# RK3562-POWER-GND.net
KiCad netlist of a schematic drawn in Altium Designer
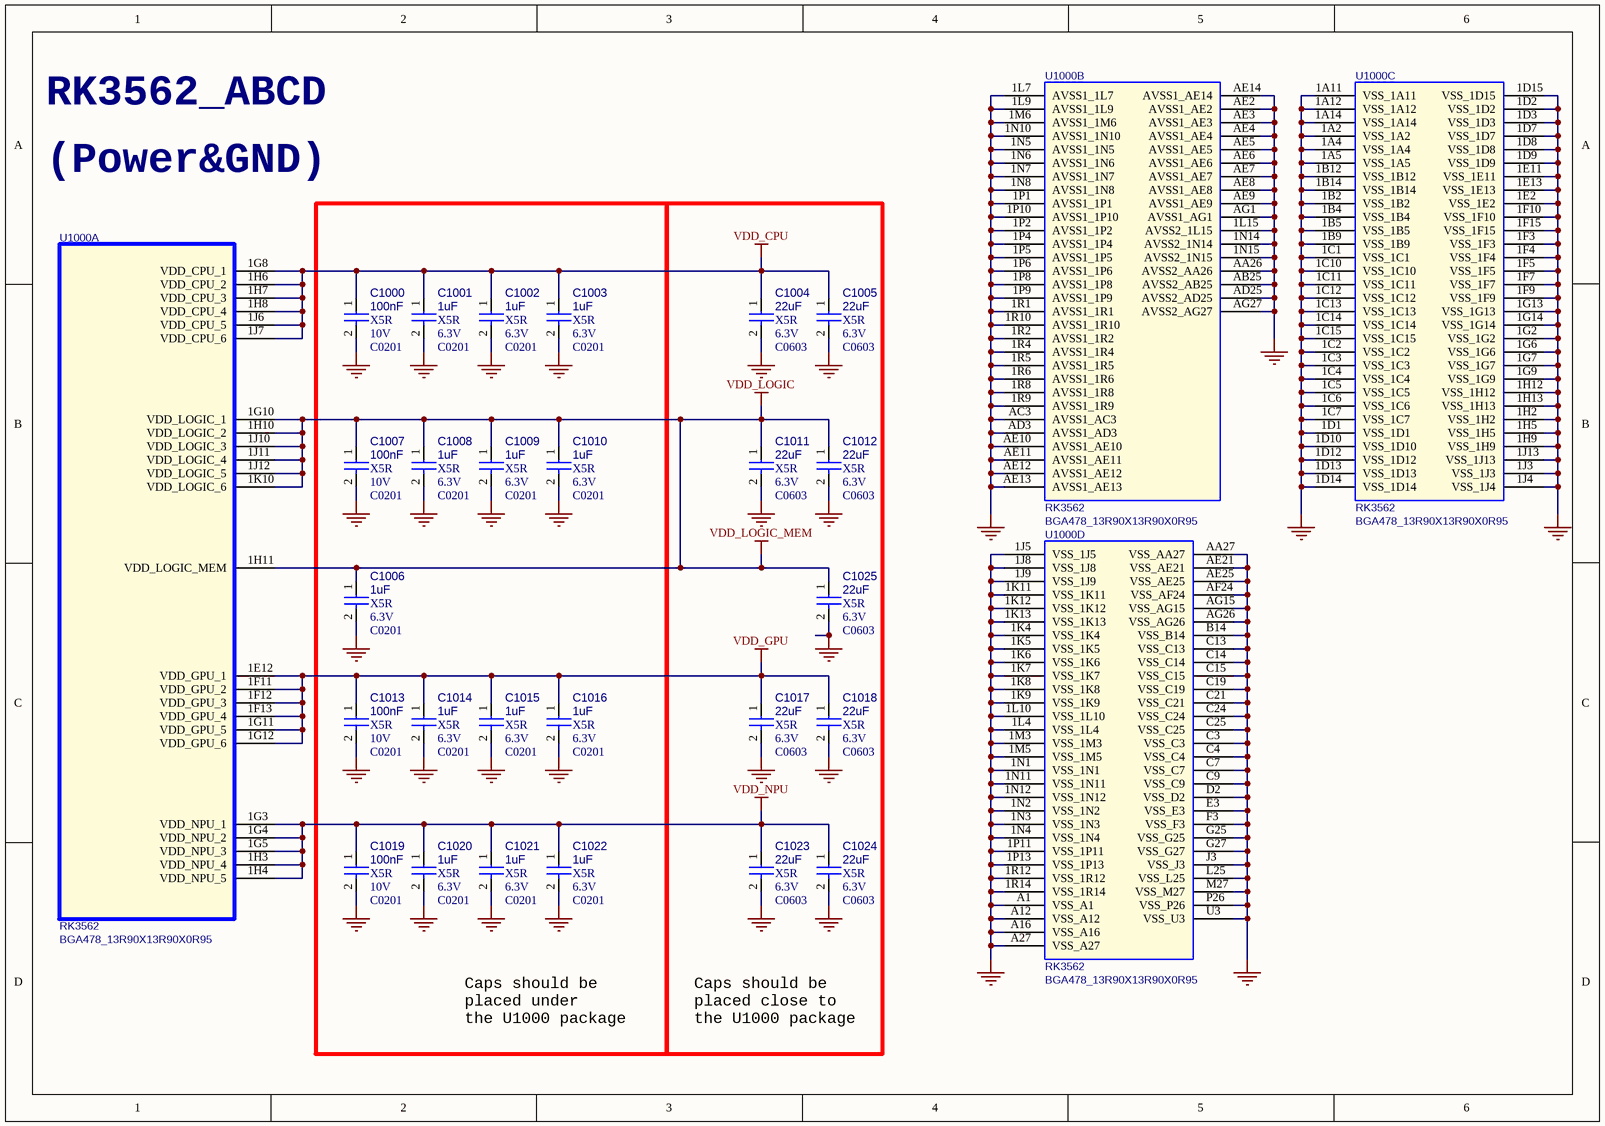
[diagram p0: RK3562-POWER-GND.SchDoc]

(export (version "E")
  (design (tool "Eeschema 10.0.6"))
  (components
    (comp (ref "C1000")
      (value "100nF")
      (footprint "C0201")
      (description "cap,100.00nF,+/-10%,10V,X5R,C0201")
      (fields
        (field (name "DIELECTRIC") "X5R")
        (field (name "PCB FOOTPRINT") "C0201")
        (field (name "VOLTAGE") "10V")
        (field (name "MANUFACTURER") "TDK")
        (field (name "TOLERANCE") "10%")
        (field (name "CREATED BY") "JJJ")
      )
      (libsource (lib "RK3562_REF") (part "CAP NP"))
    )
    (comp (ref "C1001")
      (value "1uF")
      (footprint "C0201")
      (description "cap,1.00uF,+/-20%,6.3V,X5R,C0201")
      (fields
        (field (name "DIELECTRIC") "X5R")
        (field (name "PCB FOOTPRINT") "C0201")
        (field (name "VOLTAGE") "6.3V")
        (field (name "TOLERANCE") "20%")
        (field (name "MANUFACTURER") "TDK")
        (field (name "CREATED BY") "JJJ")
      )
      (libsource (lib "RK3562_REF") (part "CAP NP"))
    )
    (comp (ref "C1002")
      (value "1uF")
      (footprint "C0201")
      (description "cap,1.00uF,+/-20%,6.3V,X5R,C0201")
      (fields
        (field (name "DIELECTRIC") "X5R")
        (field (name "PCB FOOTPRINT") "C0201")
        (field (name "VOLTAGE") "6.3V")
        (field (name "MANUFACTURER") "TDK")
        (field (name "TOLERANCE") "20%")
        (field (name "CREATED BY") "JJJ")
      )
      (libsource (lib "RK3562_REF") (part "CAP NP"))
    )
    (comp (ref "C1003")
      (value "1uF")
      (footprint "C0201")
      (description "cap,1.00uF,+/-20%,6.3V,X5R,C0201")
      (fields
        (field (name "DIELECTRIC") "X5R")
        (field (name "PCB FOOTPRINT") "C0201")
        (field (name "VOLTAGE") "6.3V")
        (field (name "MANUFACTURER") "TDK")
        (field (name "TOLERANCE") "20%")
        (field (name "CREATED BY") "JJJ")
      )
      (libsource (lib "RK3562_REF") (part "CAP NP"))
    )
    (comp (ref "C1004")
      (value "22uF")
      (footprint "C0603")
      (description "cap,22.00uF,+/-20%,6.3V,X5R,C0603")
      (fields
        (field (name "DIELECTRIC") "X5R")
        (field (name "PCB FOOTPRINT") "C0603")
        (field (name "VOLTAGE") "6.3V")
        (field (name "MANUFACTURER") "TDK")
        (field (name "TOLERANCE") "20%")
        (field (name "CREATED BY") "JJJ")
      )
      (libsource (lib "RK3562_REF") (part "CAP NP"))
    )
    (comp (ref "C1005")
      (value "22uF")
      (footprint "C0603")
      (description "cap,22.00uF,+/-20%,6.3V,X5R,C0603")
      (fields
        (field (name "DIELECTRIC") "X5R")
        (field (name "PCB FOOTPRINT") "C0603")
        (field (name "VOLTAGE") "6.3V")
        (field (name "MANUFACTURER") "TDK")
        (field (name "TOLERANCE") "20%")
        (field (name "CREATED BY") "JJJ")
      )
      (libsource (lib "RK3562_REF") (part "CAP NP"))
    )
    (comp (ref "C1006")
      (value "1uF")
      (footprint "C0201")
      (description "cap,1.00uF,+/-20%,6.3V,X5R,C0201")
      (fields
        (field (name "DIELECTRIC") "X5R")
        (field (name "PCB FOOTPRINT") "C0201")
        (field (name "VOLTAGE") "6.3V")
        (field (name "MANUFACTURER") "TDK")
        (field (name "TOLERANCE") "20%")
        (field (name "CREATED BY") "JJJ")
      )
      (libsource (lib "RK3562_REF") (part "CAP NP"))
    )
    (comp (ref "C1007")
      (value "100nF")
      (footprint "C0201")
      (description "cap,100.00nF,+/-10%,10V,X5R,C0201")
      (fields
        (field (name "DIELECTRIC") "X5R")
        (field (name "PCB FOOTPRINT") "C0201")
        (field (name "VOLTAGE") "10V")
        (field (name "MANUFACTURER") "TDK")
        (field (name "TOLERANCE") "10%")
        (field (name "CREATED BY") "JJJ")
      )
      (libsource (lib "RK3562_REF") (part "CAP NP"))
    )
    (comp (ref "C1008")
      (value "1uF")
      (footprint "C0201")
      (description "cap,1.00uF,+/-20%,6.3V,X5R,C0201")
      (fields
        (field (name "DIELECTRIC") "X5R")
        (field (name "PCB FOOTPRINT") "C0201")
        (field (name "VOLTAGE") "6.3V")
        (field (name "TOLERANCE") "20%")
        (field (name "MANUFACTURER") "TDK")
        (field (name "CREATED BY") "JJJ")
      )
      (libsource (lib "RK3562_REF") (part "CAP NP"))
    )
    (comp (ref "C1009")
      (value "1uF")
      (footprint "C0201")
      (description "cap,1.00uF,+/-20%,6.3V,X5R,C0201")
      (fields
        (field (name "DIELECTRIC") "X5R")
        (field (name "PCB FOOTPRINT") "C0201")
        (field (name "VOLTAGE") "6.3V")
        (field (name "MANUFACTURER") "TDK")
        (field (name "TOLERANCE") "20%")
        (field (name "CREATED BY") "JJJ")
      )
      (libsource (lib "RK3562_REF") (part "CAP NP"))
    )
    (comp (ref "C1010")
      (value "1uF")
      (footprint "C0201")
      (description "cap,1.00uF,+/-20%,6.3V,X5R,C0201")
      (fields
        (field (name "DIELECTRIC") "X5R")
        (field (name "PCB FOOTPRINT") "C0201")
        (field (name "VOLTAGE") "6.3V")
        (field (name "MANUFACTURER") "TDK")
        (field (name "TOLERANCE") "20%")
        (field (name "CREATED BY") "JJJ")
      )
      (libsource (lib "RK3562_REF") (part "CAP NP"))
    )
    (comp (ref "C1011")
      (value "22uF")
      (footprint "C0603")
      (description "cap,22.00uF,+/-20%,6.3V,X5R,C0603")
      (fields
        (field (name "DIELECTRIC") "X5R")
        (field (name "PCB FOOTPRINT") "C0603")
        (field (name "VOLTAGE") "6.3V")
        (field (name "MANUFACTURER") "TDK")
        (field (name "TOLERANCE") "20%")
        (field (name "CREATED BY") "JJJ")
      )
      (libsource (lib "RK3562_REF") (part "CAP NP"))
    )
    (comp (ref "C1012")
      (value "22uF")
      (footprint "C0603")
      (description "cap,22.00uF,+/-20%,6.3V,X5R,C0603")
      (fields
        (field (name "DIELECTRIC") "X5R")
        (field (name "PCB FOOTPRINT") "C0603")
        (field (name "VOLTAGE") "6.3V")
        (field (name "MANUFACTURER") "TDK")
        (field (name "TOLERANCE") "20%")
        (field (name "CREATED BY") "JJJ")
      )
      (libsource (lib "RK3562_REF") (part "CAP NP"))
    )
    (comp (ref "C1013")
      (value "100nF")
      (footprint "C0201")
      (description "cap,100.00nF,+/-10%,10V,X5R,C0201")
      (fields
        (field (name "DIELECTRIC") "X5R")
        (field (name "PCB FOOTPRINT") "C0201")
        (field (name "VOLTAGE") "10V")
        (field (name "MANUFACTURER") "TDK")
        (field (name "TOLERANCE") "10%")
        (field (name "CREATED BY") "JJJ")
      )
      (libsource (lib "RK3562_REF") (part "CAP NP"))
    )
    (comp (ref "C1014")
      (value "1uF")
      (footprint "C0201")
      (description "cap,1.00uF,+/-20%,6.3V,X5R,C0201")
      (fields
        (field (name "DIELECTRIC") "X5R")
        (field (name "PCB FOOTPRINT") "C0201")
        (field (name "VOLTAGE") "6.3V")
        (field (name "TOLERANCE") "20%")
        (field (name "MANUFACTURER") "TDK")
        (field (name "CREATED BY") "JJJ")
      )
      (libsource (lib "RK3562_REF") (part "CAP NP"))
    )
    (comp (ref "C1015")
      (value "1uF")
      (footprint "C0201")
      (description "cap,1.00uF,+/-20%,6.3V,X5R,C0201")
      (fields
        (field (name "DIELECTRIC") "X5R")
        (field (name "PCB FOOTPRINT") "C0201")
        (field (name "VOLTAGE") "6.3V")
        (field (name "MANUFACTURER") "TDK")
        (field (name "TOLERANCE") "20%")
        (field (name "CREATED BY") "JJJ")
      )
      (libsource (lib "RK3562_REF") (part "CAP NP"))
    )
    (comp (ref "C1016")
      (value "1uF")
      (footprint "C0201")
      (description "cap,1.00uF,+/-20%,6.3V,X5R,C0201")
      (fields
        (field (name "DIELECTRIC") "X5R")
        (field (name "PCB FOOTPRINT") "C0201")
        (field (name "VOLTAGE") "6.3V")
        (field (name "MANUFACTURER") "TDK")
        (field (name "TOLERANCE") "20%")
        (field (name "CREATED BY") "JJJ")
      )
      (libsource (lib "RK3562_REF") (part "CAP NP"))
    )
    (comp (ref "C1017")
      (value "22uF")
      (footprint "C0603")
      (description "cap,22.00uF,+/-20%,6.3V,X5R,C0603")
      (fields
        (field (name "DIELECTRIC") "X5R")
        (field (name "PCB FOOTPRINT") "C0603")
        (field (name "VOLTAGE") "6.3V")
        (field (name "MANUFACTURER") "TDK")
        (field (name "TOLERANCE") "20%")
        (field (name "CREATED BY") "JJJ")
      )
      (libsource (lib "RK3562_REF") (part "CAP NP"))
    )
    (comp (ref "C1018")
      (value "22uF")
      (footprint "C0603")
      (description "cap,22.00uF,+/-20%,6.3V,X5R,C0603")
      (fields
        (field (name "DIELECTRIC") "X5R")
        (field (name "PCB FOOTPRINT") "C0603")
        (field (name "VOLTAGE") "6.3V")
        (field (name "MANUFACTURER") "TDK")
        (field (name "TOLERANCE") "20%")
        (field (name "CREATED BY") "JJJ")
      )
      (libsource (lib "RK3562_REF") (part "CAP NP"))
    )
    (comp (ref "C1019")
      (value "100nF")
      (footprint "C0201")
      (description "cap,100.00nF,+/-10%,10V,X5R,C0201")
      (fields
        (field (name "DIELECTRIC") "X5R")
        (field (name "PCB FOOTPRINT") "C0201")
        (field (name "VOLTAGE") "10V")
        (field (name "MANUFACTURER") "TDK")
        (field (name "TOLERANCE") "10%")
        (field (name "CREATED BY") "JJJ")
      )
      (libsource (lib "RK3562_REF") (part "CAP NP"))
    )
    (comp (ref "C1020")
      (value "1uF")
      (footprint "C0201")
      (description "cap,1.00uF,+/-20%,6.3V,X5R,C0201")
      (fields
        (field (name "DIELECTRIC") "X5R")
        (field (name "PCB FOOTPRINT") "C0201")
        (field (name "VOLTAGE") "6.3V")
        (field (name "TOLERANCE") "20%")
        (field (name "MANUFACTURER") "TDK")
        (field (name "CREATED BY") "JJJ")
      )
      (libsource (lib "RK3562_REF") (part "CAP NP"))
    )
    (comp (ref "C1021")
      (value "1uF")
      (footprint "C0201")
      (description "cap,1.00uF,+/-20%,6.3V,X5R,C0201")
      (fields
        (field (name "DIELECTRIC") "X5R")
        (field (name "PCB FOOTPRINT") "C0201")
        (field (name "VOLTAGE") "6.3V")
        (field (name "MANUFACTURER") "TDK")
        (field (name "TOLERANCE") "20%")
        (field (name "CREATED BY") "JJJ")
      )
      (libsource (lib "RK3562_REF") (part "CAP NP"))
    )
    (comp (ref "C1022")
      (value "1uF")
      (footprint "C0201")
      (description "cap,1.00uF,+/-20%,6.3V,X5R,C0201")
      (fields
        (field (name "DIELECTRIC") "X5R")
        (field (name "PCB FOOTPRINT") "C0201")
        (field (name "VOLTAGE") "6.3V")
        (field (name "TOLERANCE") "20%")
        (field (name "MANUFACTURER") "TDK")
        (field (name "CREATED BY") "JJJ")
      )
      (libsource (lib "RK3562_REF") (part "CAP NP"))
    )
    (comp (ref "C1023")
      (value "22uF")
      (footprint "C0603")
      (description "cap,22.00uF,+/-20%,6.3V,X5R,C0603")
      (fields
        (field (name "DIELECTRIC") "X5R")
        (field (name "PCB FOOTPRINT") "C0603")
        (field (name "VOLTAGE") "6.3V")
        (field (name "MANUFACTURER") "TDK")
        (field (name "TOLERANCE") "20%")
        (field (name "CREATED BY") "JJJ")
      )
      (libsource (lib "RK3562_REF") (part "CAP NP"))
    )
    (comp (ref "C1024")
      (value "22uF")
      (footprint "C0603")
      (description "cap,22.00uF,+/-20%,6.3V,X5R,C0603")
      (fields
        (field (name "DIELECTRIC") "X5R")
        (field (name "PCB FOOTPRINT") "C0603")
        (field (name "VOLTAGE") "6.3V")
        (field (name "MANUFACTURER") "TDK")
        (field (name "TOLERANCE") "20%")
        (field (name "CREATED BY") "JJJ")
      )
      (libsource (lib "RK3562_REF") (part "CAP NP"))
    )
    (comp (ref "C1025")
      (value "22uF")
      (footprint "C0603")
      (description "cap,22.00uF,+/-20%,6.3V,X5R,C0603")
      (fields
        (field (name "DIELECTRIC") "X5R")
        (field (name "PCB FOOTPRINT") "C0603")
        (field (name "VOLTAGE") "6.3V")
        (field (name "TOLERANCE") "20%")
        (field (name "MANUFACTURER") "TDK")
        (field (name "CREATED BY") "JJJ")
      )
      (libsource (lib "RK3562_REF") (part "CAP NP"))
    )
    (comp (ref "U1000")
      (value "RK3562")
      (footprint "BGA478_13R90X13R90X0R95")
      (description "ROCKCHIP SOC")
      (fields
        (field (name "PCB FOOTPRINT") "BGA478_13R90X13R90X0R95")
        (field (name "MANUFACTURER") "Rockchip (瑞芯微)")
        (field (name "CREATED BY") "JJJ")
      )
      (libsource (lib "RK3562_REF") (part "SOC_RK3562"))
    )
  )
  (nets
    (net (code "1") (name "GND") (class "Default")
      (node (ref "C1000") (pin "2") (pinfunction "2_2") (pintype "passive"))
      (node (ref "C1001") (pin "2") (pinfunction "2_2") (pintype "passive"))
      (node (ref "C1002") (pin "2") (pinfunction "2_2") (pintype "passive"))
      (node (ref "C1003") (pin "2") (pinfunction "2_2") (pintype "passive"))
      (node (ref "C1004") (pin "2") (pinfunction "2_2") (pintype "passive"))
      (node (ref "C1005") (pin "2") (pinfunction "2_2") (pintype "passive"))
      (node (ref "C1006") (pin "2") (pinfunction "2_2") (pintype "passive"))
      (node (ref "C1007") (pin "2") (pinfunction "2_2") (pintype "passive"))
      (node (ref "C1008") (pin "2") (pinfunction "2_2") (pintype "passive"))
      (node (ref "C1009") (pin "2") (pinfunction "2_2") (pintype "passive"))
      (node (ref "C1010") (pin "2") (pinfunction "2_2") (pintype "passive"))
      (node (ref "C1011") (pin "2") (pinfunction "2_2") (pintype "passive"))
      (node (ref "C1012") (pin "2") (pinfunction "2_2") (pintype "passive"))
      (node (ref "C1013") (pin "2") (pinfunction "2_2") (pintype "passive"))
      (node (ref "C1014") (pin "2") (pinfunction "2_2") (pintype "passive"))
      (node (ref "C1015") (pin "2") (pinfunction "2_2") (pintype "passive"))
      (node (ref "C1016") (pin "2") (pinfunction "2_2") (pintype "passive"))
      (node (ref "C1017") (pin "2") (pinfunction "2_2") (pintype "passive"))
      (node (ref "C1018") (pin "2") (pinfunction "2_2") (pintype "passive"))
      (node (ref "C1019") (pin "2") (pinfunction "2_2") (pintype "passive"))
      (node (ref "C1020") (pin "2") (pinfunction "2_2") (pintype "passive"))
      (node (ref "C1021") (pin "2") (pinfunction "2_2") (pintype "passive"))
      (node (ref "C1022") (pin "2") (pinfunction "2_2") (pintype "passive"))
      (node (ref "C1023") (pin "2") (pinfunction "2_2") (pintype "passive"))
      (node (ref "C1024") (pin "2") (pinfunction "2_2") (pintype "passive"))
      (node (ref "C1025") (pin "2") (pinfunction "2_2") (pintype "passive"))
      (node (ref "U1000") (pin "1A11") (pinfunction "VSS_1A11_1A11") (pintype "passive"))
      (node (ref "U1000") (pin "1A12") (pinfunction "VSS_1A12_1A12") (pintype "passive"))
      (node (ref "U1000") (pin "1A14") (pinfunction "VSS_1A14_1A14") (pintype "passive"))
      (node (ref "U1000") (pin "1A2") (pinfunction "VSS_1A2_1A2") (pintype "passive"))
      (node (ref "U1000") (pin "1A4") (pinfunction "VSS_1A4_1A4") (pintype "passive"))
      (node (ref "U1000") (pin "1A5") (pinfunction "VSS_1A5_1A5") (pintype "passive"))
      (node (ref "U1000") (pin "1B12") (pinfunction "VSS_1B12_1B12") (pintype "passive"))
      (node (ref "U1000") (pin "1B14") (pinfunction "VSS_1B14_1B14") (pintype "passive"))
      (node (ref "U1000") (pin "1B2") (pinfunction "VSS_1B2_1B2") (pintype "passive"))
      (node (ref "U1000") (pin "1B4") (pinfunction "VSS_1B4_1B4") (pintype "passive"))
      (node (ref "U1000") (pin "1B5") (pinfunction "VSS_1B5_1B5") (pintype "passive"))
      (node (ref "U1000") (pin "1B9") (pinfunction "VSS_1B9_1B9") (pintype "passive"))
      (node (ref "U1000") (pin "1C1") (pinfunction "VSS_1C1_1C1") (pintype "passive"))
      (node (ref "U1000") (pin "1C10") (pinfunction "VSS_1C10_1C10") (pintype "passive"))
      (node (ref "U1000") (pin "1C11") (pinfunction "VSS_1C11_1C11") (pintype "passive"))
      (node (ref "U1000") (pin "1C12") (pinfunction "VSS_1C12_1C12") (pintype "passive"))
      (node (ref "U1000") (pin "1C13") (pinfunction "VSS_1C13_1C13") (pintype "passive"))
      (node (ref "U1000") (pin "1C14") (pinfunction "VSS_1C14_1C14") (pintype "passive"))
      (node (ref "U1000") (pin "1C15") (pinfunction "VSS_1C15_1C15") (pintype "passive"))
      (node (ref "U1000") (pin "1C2") (pinfunction "VSS_1C2_1C2") (pintype "passive"))
      (node (ref "U1000") (pin "1C3") (pinfunction "VSS_1C3_1C3") (pintype "passive"))
      (node (ref "U1000") (pin "1C4") (pinfunction "VSS_1C4_1C4") (pintype "passive"))
      (node (ref "U1000") (pin "1C5") (pinfunction "VSS_1C5_1C5") (pintype "passive"))
      (node (ref "U1000") (pin "1C6") (pinfunction "VSS_1C6_1C6") (pintype "passive"))
      (node (ref "U1000") (pin "1C7") (pinfunction "VSS_1C7_1C7") (pintype "passive"))
      (node (ref "U1000") (pin "1D1") (pinfunction "VSS_1D1_1D1") (pintype "passive"))
      (node (ref "U1000") (pin "1D10") (pinfunction "VSS_1D10_1D10") (pintype "passive"))
      (node (ref "U1000") (pin "1D12") (pinfunction "VSS_1D12_1D12") (pintype "passive"))
      (node (ref "U1000") (pin "1D13") (pinfunction "VSS_1D13_1D13") (pintype "passive"))
      (node (ref "U1000") (pin "1D14") (pinfunction "VSS_1D14_1D14") (pintype "passive"))
      (node (ref "U1000") (pin "1D15") (pinfunction "VSS_1D15_1D15") (pintype "passive"))
      (node (ref "U1000") (pin "1D2") (pinfunction "VSS_1D2_1D2") (pintype "passive"))
      (node (ref "U1000") (pin "1D3") (pinfunction "VSS_1D3_1D3") (pintype "passive"))
      (node (ref "U1000") (pin "1D7") (pinfunction "VSS_1D7_1D7") (pintype "passive"))
      (node (ref "U1000") (pin "1D8") (pinfunction "VSS_1D8_1D8") (pintype "passive"))
      (node (ref "U1000") (pin "1D9") (pinfunction "VSS_1D9_1D9") (pintype "passive"))
      (node (ref "U1000") (pin "1E11") (pinfunction "VSS_1E11_1E11") (pintype "passive"))
      (node (ref "U1000") (pin "1E13") (pinfunction "VSS_1E13_1E13") (pintype "passive"))
      (node (ref "U1000") (pin "1E2") (pinfunction "VSS_1E2_1E2") (pintype "passive"))
      (node (ref "U1000") (pin "1F10") (pinfunction "VSS_1F10_1F10") (pintype "passive"))
      (node (ref "U1000") (pin "1F15") (pinfunction "VSS_1F15_1F15") (pintype "passive"))
      (node (ref "U1000") (pin "1F3") (pinfunction "VSS_1F3_1F3") (pintype "passive"))
      (node (ref "U1000") (pin "1F4") (pinfunction "VSS_1F4_1F4") (pintype "passive"))
      (node (ref "U1000") (pin "1F5") (pinfunction "VSS_1F5_1F5") (pintype "passive"))
      (node (ref "U1000") (pin "1F7") (pinfunction "VSS_1F7_1F7") (pintype "passive"))
      (node (ref "U1000") (pin "1F9") (pinfunction "VSS_1F9_1F9") (pintype "passive"))
      (node (ref "U1000") (pin "1G13") (pinfunction "VSS_1G13_1G13") (pintype "passive"))
      (node (ref "U1000") (pin "1G14") (pinfunction "VSS_1G14_1G14") (pintype "passive"))
      (node (ref "U1000") (pin "1G2") (pinfunction "VSS_1G2_1G2") (pintype "passive"))
      (node (ref "U1000") (pin "1G6") (pinfunction "VSS_1G6_1G6") (pintype "passive"))
      (node (ref "U1000") (pin "1G7") (pinfunction "VSS_1G7_1G7") (pintype "passive"))
      (node (ref "U1000") (pin "1G9") (pinfunction "VSS_1G9_1G9") (pintype "passive"))
      (node (ref "U1000") (pin "1H12") (pinfunction "VSS_1H12_1H12") (pintype "passive"))
      (node (ref "U1000") (pin "1H13") (pinfunction "VSS_1H13_1H13") (pintype "passive"))
      (node (ref "U1000") (pin "1H2") (pinfunction "VSS_1H2_1H2") (pintype "passive"))
      (node (ref "U1000") (pin "1H5") (pinfunction "VSS_1H5_1H5") (pintype "passive"))
      (node (ref "U1000") (pin "1H9") (pinfunction "VSS_1H9_1H9") (pintype "passive"))
      (node (ref "U1000") (pin "1J13") (pinfunction "VSS_1J13_1J13") (pintype "passive"))
      (node (ref "U1000") (pin "1J3") (pinfunction "VSS_1J3_1J3") (pintype "passive"))
      (node (ref "U1000") (pin "1J4") (pinfunction "VSS_1J4_1J4") (pintype "passive"))
      (node (ref "U1000") (pin "1J5") (pinfunction "VSS_1J5_1J5") (pintype "passive"))
      (node (ref "U1000") (pin "1J8") (pinfunction "VSS_1J8_1J8") (pintype "passive"))
      (node (ref "U1000") (pin "1J9") (pinfunction "VSS_1J9_1J9") (pintype "passive"))
      (node (ref "U1000") (pin "1K11") (pinfunction "VSS_1K11_1K11") (pintype "passive"))
      (node (ref "U1000") (pin "1K12") (pinfunction "VSS_1K12_1K12") (pintype "passive"))
      (node (ref "U1000") (pin "1K13") (pinfunction "VSS_1K13_1K13") (pintype "passive"))
      (node (ref "U1000") (pin "1K4") (pinfunction "VSS_1K4_1K4") (pintype "passive"))
      (node (ref "U1000") (pin "1K5") (pinfunction "VSS_1K5_1K5") (pintype "passive"))
      (node (ref "U1000") (pin "1K6") (pinfunction "VSS_1K6_1K6") (pintype "passive"))
      (node (ref "U1000") (pin "1K7") (pinfunction "VSS_1K7_1K7") (pintype "passive"))
      (node (ref "U1000") (pin "1K8") (pinfunction "VSS_1K8_1K8") (pintype "passive"))
      (node (ref "U1000") (pin "1K9") (pinfunction "VSS_1K9_1K9") (pintype "passive"))
      (node (ref "U1000") (pin "1L10") (pinfunction "VSS_1L10_1L10") (pintype "passive"))
      (node (ref "U1000") (pin "1L15") (pinfunction "AVSS2_1L15_1L15") (pintype "passive"))
      (node (ref "U1000") (pin "1L4") (pinfunction "VSS_1L4_1L4") (pintype "passive"))
      (node (ref "U1000") (pin "1L7") (pinfunction "AVSS1_1L7_1L7") (pintype "passive"))
      (node (ref "U1000") (pin "1L9") (pinfunction "AVSS1_1L9_1L9") (pintype "passive"))
      (node (ref "U1000") (pin "1M3") (pinfunction "VSS_1M3_1M3") (pintype "passive"))
      (node (ref "U1000") (pin "1M5") (pinfunction "VSS_1M5_1M5") (pintype "passive"))
      (node (ref "U1000") (pin "1M6") (pinfunction "AVSS1_1M6_1M6") (pintype "passive"))
      (node (ref "U1000") (pin "1N1") (pinfunction "VSS_1N1_1N1") (pintype "passive"))
      (node (ref "U1000") (pin "1N10") (pinfunction "AVSS1_1N10_1N10") (pintype "passive"))
      (node (ref "U1000") (pin "1N11") (pinfunction "VSS_1N11_1N11") (pintype "passive"))
      (node (ref "U1000") (pin "1N12") (pinfunction "VSS_1N12_1N12") (pintype "passive"))
      (node (ref "U1000") (pin "1N14") (pinfunction "AVSS2_1N14_1N14") (pintype "passive"))
      (node (ref "U1000") (pin "1N15") (pinfunction "AVSS2_1N15_1N15") (pintype "passive"))
      (node (ref "U1000") (pin "1N2") (pinfunction "VSS_1N2_1N2") (pintype "passive"))
      (node (ref "U1000") (pin "1N3") (pinfunction "VSS_1N3_1N3") (pintype "passive"))
      (node (ref "U1000") (pin "1N4") (pinfunction "VSS_1N4_1N4") (pintype "passive"))
      (node (ref "U1000") (pin "1N5") (pinfunction "AVSS1_1N5_1N5") (pintype "passive"))
      (node (ref "U1000") (pin "1N6") (pinfunction "AVSS1_1N6_1N6") (pintype "passive"))
      (node (ref "U1000") (pin "1N7") (pinfunction "AVSS1_1N7_1N7") (pintype "passive"))
      (node (ref "U1000") (pin "1N8") (pinfunction "AVSS1_1N8_1N8") (pintype "passive"))
      (node (ref "U1000") (pin "1P1") (pinfunction "AVSS1_1P1_1P1") (pintype "passive"))
      (node (ref "U1000") (pin "1P10") (pinfunction "AVSS1_1P10_1P10") (pintype "passive"))
      (node (ref "U1000") (pin "1P11") (pinfunction "VSS_1P11_1P11") (pintype "passive"))
      (node (ref "U1000") (pin "1P13") (pinfunction "VSS_1P13_1P13") (pintype "passive"))
      (node (ref "U1000") (pin "1P2") (pinfunction "AVSS1_1P2_1P2") (pintype "passive"))
      (node (ref "U1000") (pin "1P4") (pinfunction "AVSS1_1P4_1P4") (pintype "passive"))
      (node (ref "U1000") (pin "1P5") (pinfunction "AVSS1_1P5_1P5") (pintype "passive"))
      (node (ref "U1000") (pin "1P6") (pinfunction "AVSS1_1P6_1P6") (pintype "passive"))
      (node (ref "U1000") (pin "1P8") (pinfunction "AVSS1_1P8_1P8") (pintype "passive"))
      (node (ref "U1000") (pin "1P9") (pinfunction "AVSS1_1P9_1P9") (pintype "passive"))
      (node (ref "U1000") (pin "1R1") (pinfunction "AVSS1_1R1_1R1") (pintype "passive"))
      (node (ref "U1000") (pin "1R10") (pinfunction "AVSS1_1R10_1R10") (pintype "passive"))
      (node (ref "U1000") (pin "1R12") (pinfunction "VSS_1R12_1R12") (pintype "passive"))
      (node (ref "U1000") (pin "1R14") (pinfunction "VSS_1R14_1R14") (pintype "passive"))
      (node (ref "U1000") (pin "1R2") (pinfunction "AVSS1_1R2_1R2") (pintype "passive"))
      (node (ref "U1000") (pin "1R4") (pinfunction "AVSS1_1R4_1R4") (pintype "passive"))
      (node (ref "U1000") (pin "1R5") (pinfunction "AVSS1_1R5_1R5") (pintype "passive"))
      (node (ref "U1000") (pin "1R6") (pinfunction "AVSS1_1R6_1R6") (pintype "passive"))
      (node (ref "U1000") (pin "1R8") (pinfunction "AVSS1_1R8_1R8") (pintype "passive"))
      (node (ref "U1000") (pin "1R9") (pinfunction "AVSS1_1R9_1R9") (pintype "passive"))
      (node (ref "U1000") (pin "A1") (pinfunction "VSS_A1_A1") (pintype "passive"))
      (node (ref "U1000") (pin "A12") (pinfunction "VSS_A12_A12") (pintype "passive"))
      (node (ref "U1000") (pin "A16") (pinfunction "VSS_A16_A16") (pintype "passive"))
      (node (ref "U1000") (pin "A27") (pinfunction "VSS_A27_A27") (pintype "passive"))
      (node (ref "U1000") (pin "AA26") (pinfunction "AVSS2_AA26_AA26") (pintype "passive"))
      (node (ref "U1000") (pin "AA27") (pinfunction "VSS_AA27_AA27") (pintype "passive"))
      (node (ref "U1000") (pin "AB25") (pinfunction "AVSS2_AB25_AB25") (pintype "passive"))
      (node (ref "U1000") (pin "AC3") (pinfunction "AVSS1_AC3_AC3") (pintype "passive"))
      (node (ref "U1000") (pin "AD25") (pinfunction "AVSS2_AD25_AD25") (pintype "passive"))
      (node (ref "U1000") (pin "AD3") (pinfunction "AVSS1_AD3_AD3") (pintype "passive"))
      (node (ref "U1000") (pin "AE10") (pinfunction "AVSS1_AE10_AE10") (pintype "passive"))
      (node (ref "U1000") (pin "AE11") (pinfunction "AVSS1_AE11_AE11") (pintype "passive"))
      (node (ref "U1000") (pin "AE12") (pinfunction "AVSS1_AE12_AE12") (pintype "passive"))
      (node (ref "U1000") (pin "AE13") (pinfunction "AVSS1_AE13_AE13") (pintype "passive"))
      (node (ref "U1000") (pin "AE14") (pinfunction "AVSS1_AE14_AE14") (pintype "passive"))
      (node (ref "U1000") (pin "AE2") (pinfunction "AVSS1_AE2_AE2") (pintype "passive"))
      (node (ref "U1000") (pin "AE21") (pinfunction "VSS_AE21_AE21") (pintype "passive"))
      (node (ref "U1000") (pin "AE25") (pinfunction "VSS_AE25_AE25") (pintype "passive"))
      (node (ref "U1000") (pin "AE3") (pinfunction "AVSS1_AE3_AE3") (pintype "passive"))
      (node (ref "U1000") (pin "AE4") (pinfunction "AVSS1_AE4_AE4") (pintype "passive"))
      (node (ref "U1000") (pin "AE5") (pinfunction "AVSS1_AE5_AE5") (pintype "passive"))
      (node (ref "U1000") (pin "AE6") (pinfunction "AVSS1_AE6_AE6") (pintype "passive"))
      (node (ref "U1000") (pin "AE7") (pinfunction "AVSS1_AE7_AE7") (pintype "passive"))
      (node (ref "U1000") (pin "AE8") (pinfunction "AVSS1_AE8_AE8") (pintype "passive"))
      (node (ref "U1000") (pin "AE9") (pinfunction "AVSS1_AE9_AE9") (pintype "passive"))
      (node (ref "U1000") (pin "AF24") (pinfunction "VSS_AF24_AF24") (pintype "passive"))
      (node (ref "U1000") (pin "AG1") (pinfunction "AVSS1_AG1_AG1") (pintype "passive"))
      (node (ref "U1000") (pin "AG15") (pinfunction "VSS_AG15_AG15") (pintype "passive"))
      (node (ref "U1000") (pin "AG26") (pinfunction "VSS_AG26_AG26") (pintype "passive"))
      (node (ref "U1000") (pin "AG27") (pinfunction "AVSS2_AG27_AG27") (pintype "passive"))
      (node (ref "U1000") (pin "B14") (pinfunction "VSS_B14_B14") (pintype "passive"))
      (node (ref "U1000") (pin "C13") (pinfunction "VSS_C13_C13") (pintype "passive"))
      (node (ref "U1000") (pin "C14") (pinfunction "VSS_C14_C14") (pintype "passive"))
      (node (ref "U1000") (pin "C15") (pinfunction "VSS_C15_C15") (pintype "passive"))
      (node (ref "U1000") (pin "C19") (pinfunction "VSS_C19_C19") (pintype "passive"))
      (node (ref "U1000") (pin "C21") (pinfunction "VSS_C21_C21") (pintype "passive"))
      (node (ref "U1000") (pin "C24") (pinfunction "VSS_C24_C24") (pintype "passive"))
      (node (ref "U1000") (pin "C25") (pinfunction "VSS_C25_C25") (pintype "passive"))
      (node (ref "U1000") (pin "C3") (pinfunction "VSS_C3_C3") (pintype "passive"))
      (node (ref "U1000") (pin "C4") (pinfunction "VSS_C4_C4") (pintype "passive"))
      (node (ref "U1000") (pin "C7") (pinfunction "VSS_C7_C7") (pintype "passive"))
      (node (ref "U1000") (pin "C9") (pinfunction "VSS_C9_C9") (pintype "passive"))
      (node (ref "U1000") (pin "D2") (pinfunction "VSS_D2_D2") (pintype "passive"))
      (node (ref "U1000") (pin "E3") (pinfunction "VSS_E3_E3") (pintype "passive"))
      (node (ref "U1000") (pin "F3") (pinfunction "VSS_F3_F3") (pintype "passive"))
      (node (ref "U1000") (pin "G25") (pinfunction "VSS_G25_G25") (pintype "passive"))
      (node (ref "U1000") (pin "G27") (pinfunction "VSS_G27_G27") (pintype "passive"))
      (node (ref "U1000") (pin "J3") (pinfunction "VSS_J3_J3") (pintype "passive"))
      (node (ref "U1000") (pin "L25") (pinfunction "VSS_L25_L25") (pintype "passive"))
      (node (ref "U1000") (pin "M27") (pinfunction "VSS_M27_M27") (pintype "passive"))
      (node (ref "U1000") (pin "P26") (pinfunction "VSS_P26_P26") (pintype "passive"))
      (node (ref "U1000") (pin "U3") (pinfunction "VSS_U3_U3") (pintype "passive"))
    )
    (net (code "2") (name "VDD_CPU") (class "Default")
      (node (ref "C1000") (pin "1") (pinfunction "1_1") (pintype "passive"))
      (node (ref "C1001") (pin "1") (pinfunction "1_1") (pintype "passive"))
      (node (ref "C1002") (pin "1") (pinfunction "1_1") (pintype "passive"))
      (node (ref "C1003") (pin "1") (pinfunction "1_1") (pintype "passive"))
      (node (ref "C1004") (pin "1") (pinfunction "1_1") (pintype "passive"))
      (node (ref "C1005") (pin "1") (pinfunction "1_1") (pintype "passive"))
      (node (ref "U1000") (pin "1G8") (pinfunction "VDD_CPU_1_1G8") (pintype "passive"))
      (node (ref "U1000") (pin "1H6") (pinfunction "VDD_CPU_2_1H6") (pintype "passive"))
      (node (ref "U1000") (pin "1H7") (pinfunction "VDD_CPU_3_1H7") (pintype "passive"))
      (node (ref "U1000") (pin "1H8") (pinfunction "VDD_CPU_4_1H8") (pintype "passive"))
      (node (ref "U1000") (pin "1J6") (pinfunction "VDD_CPU_5_1J6") (pintype "passive"))
      (node (ref "U1000") (pin "1J7") (pinfunction "VDD_CPU_6_1J7") (pintype "passive"))
    )
    (net (code "3") (name "VDD_GPU") (class "Default")
      (node (ref "C1013") (pin "1") (pinfunction "1_1") (pintype "passive"))
      (node (ref "C1014") (pin "1") (pinfunction "1_1") (pintype "passive"))
      (node (ref "C1015") (pin "1") (pinfunction "1_1") (pintype "passive"))
      (node (ref "C1016") (pin "1") (pinfunction "1_1") (pintype "passive"))
      (node (ref "C1017") (pin "1") (pinfunction "1_1") (pintype "passive"))
      (node (ref "C1018") (pin "1") (pinfunction "1_1") (pintype "passive"))
      (node (ref "U1000") (pin "1E12") (pinfunction "VDD_GPU_1_1E12") (pintype "passive"))
      (node (ref "U1000") (pin "1F11") (pinfunction "VDD_GPU_2_1F11") (pintype "passive"))
      (node (ref "U1000") (pin "1F12") (pinfunction "VDD_GPU_3_1F12") (pintype "passive"))
      (node (ref "U1000") (pin "1F13") (pinfunction "VDD_GPU_4_1F13") (pintype "passive"))
      (node (ref "U1000") (pin "1G11") (pinfunction "VDD_GPU_5_1G11") (pintype "passive"))
      (node (ref "U1000") (pin "1G12") (pinfunction "VDD_GPU_6_1G12") (pintype "passive"))
    )
    (net (code "4") (name "VDD_LOGIC") (class "Default")
      (node (ref "C1006") (pin "1") (pinfunction "1_1") (pintype "passive"))
      (node (ref "C1007") (pin "1") (pinfunction "1_1") (pintype "passive"))
      (node (ref "C1008") (pin "1") (pinfunction "1_1") (pintype "passive"))
      (node (ref "C1009") (pin "1") (pinfunction "1_1") (pintype "passive"))
      (node (ref "C1010") (pin "1") (pinfunction "1_1") (pintype "passive"))
      (node (ref "C1011") (pin "1") (pinfunction "1_1") (pintype "passive"))
      (node (ref "C1012") (pin "1") (pinfunction "1_1") (pintype "passive"))
      (node (ref "C1025") (pin "1") (pinfunction "1_1") (pintype "passive"))
      (node (ref "U1000") (pin "1G10") (pinfunction "VDD_LOGIC_1_1G10") (pintype "passive"))
      (node (ref "U1000") (pin "1H10") (pinfunction "VDD_LOGIC_2_1H10") (pintype "passive"))
      (node (ref "U1000") (pin "1H11") (pinfunction "VDD_LOGIC_MEM_1H11") (pintype "passive"))
      (node (ref "U1000") (pin "1J10") (pinfunction "VDD_LOGIC_3_1J10") (pintype "passive"))
      (node (ref "U1000") (pin "1J11") (pinfunction "VDD_LOGIC_4_1J11") (pintype "passive"))
      (node (ref "U1000") (pin "1J12") (pinfunction "VDD_LOGIC_5_1J12") (pintype "passive"))
      (node (ref "U1000") (pin "1K10") (pinfunction "VDD_LOGIC_6_1K10") (pintype "passive"))
    )
    (net (code "5") (name "VDD_NPU") (class "Default")
      (node (ref "C1019") (pin "1") (pinfunction "1_1") (pintype "passive"))
      (node (ref "C1020") (pin "1") (pinfunction "1_1") (pintype "passive"))
      (node (ref "C1021") (pin "1") (pinfunction "1_1") (pintype "passive"))
      (node (ref "C1022") (pin "1") (pinfunction "1_1") (pintype "passive"))
      (node (ref "C1023") (pin "1") (pinfunction "1_1") (pintype "passive"))
      (node (ref "C1024") (pin "1") (pinfunction "1_1") (pintype "passive"))
      (node (ref "U1000") (pin "1G3") (pinfunction "VDD_NPU_1_1G3") (pintype "passive"))
      (node (ref "U1000") (pin "1G4") (pinfunction "VDD_NPU_2_1G4") (pintype "passive"))
      (node (ref "U1000") (pin "1G5") (pinfunction "VDD_NPU_3_1G5") (pintype "passive"))
      (node (ref "U1000") (pin "1H3") (pinfunction "VDD_NPU_4_1H3") (pintype "passive"))
      (node (ref "U1000") (pin "1H4") (pinfunction "VDD_NPU_5_1H4") (pintype "passive"))
    )
  )
)
